# Adafruit_Proto_Doubler_PiCowbell.net
KiCad netlist of a schematic drawn in EAGLE
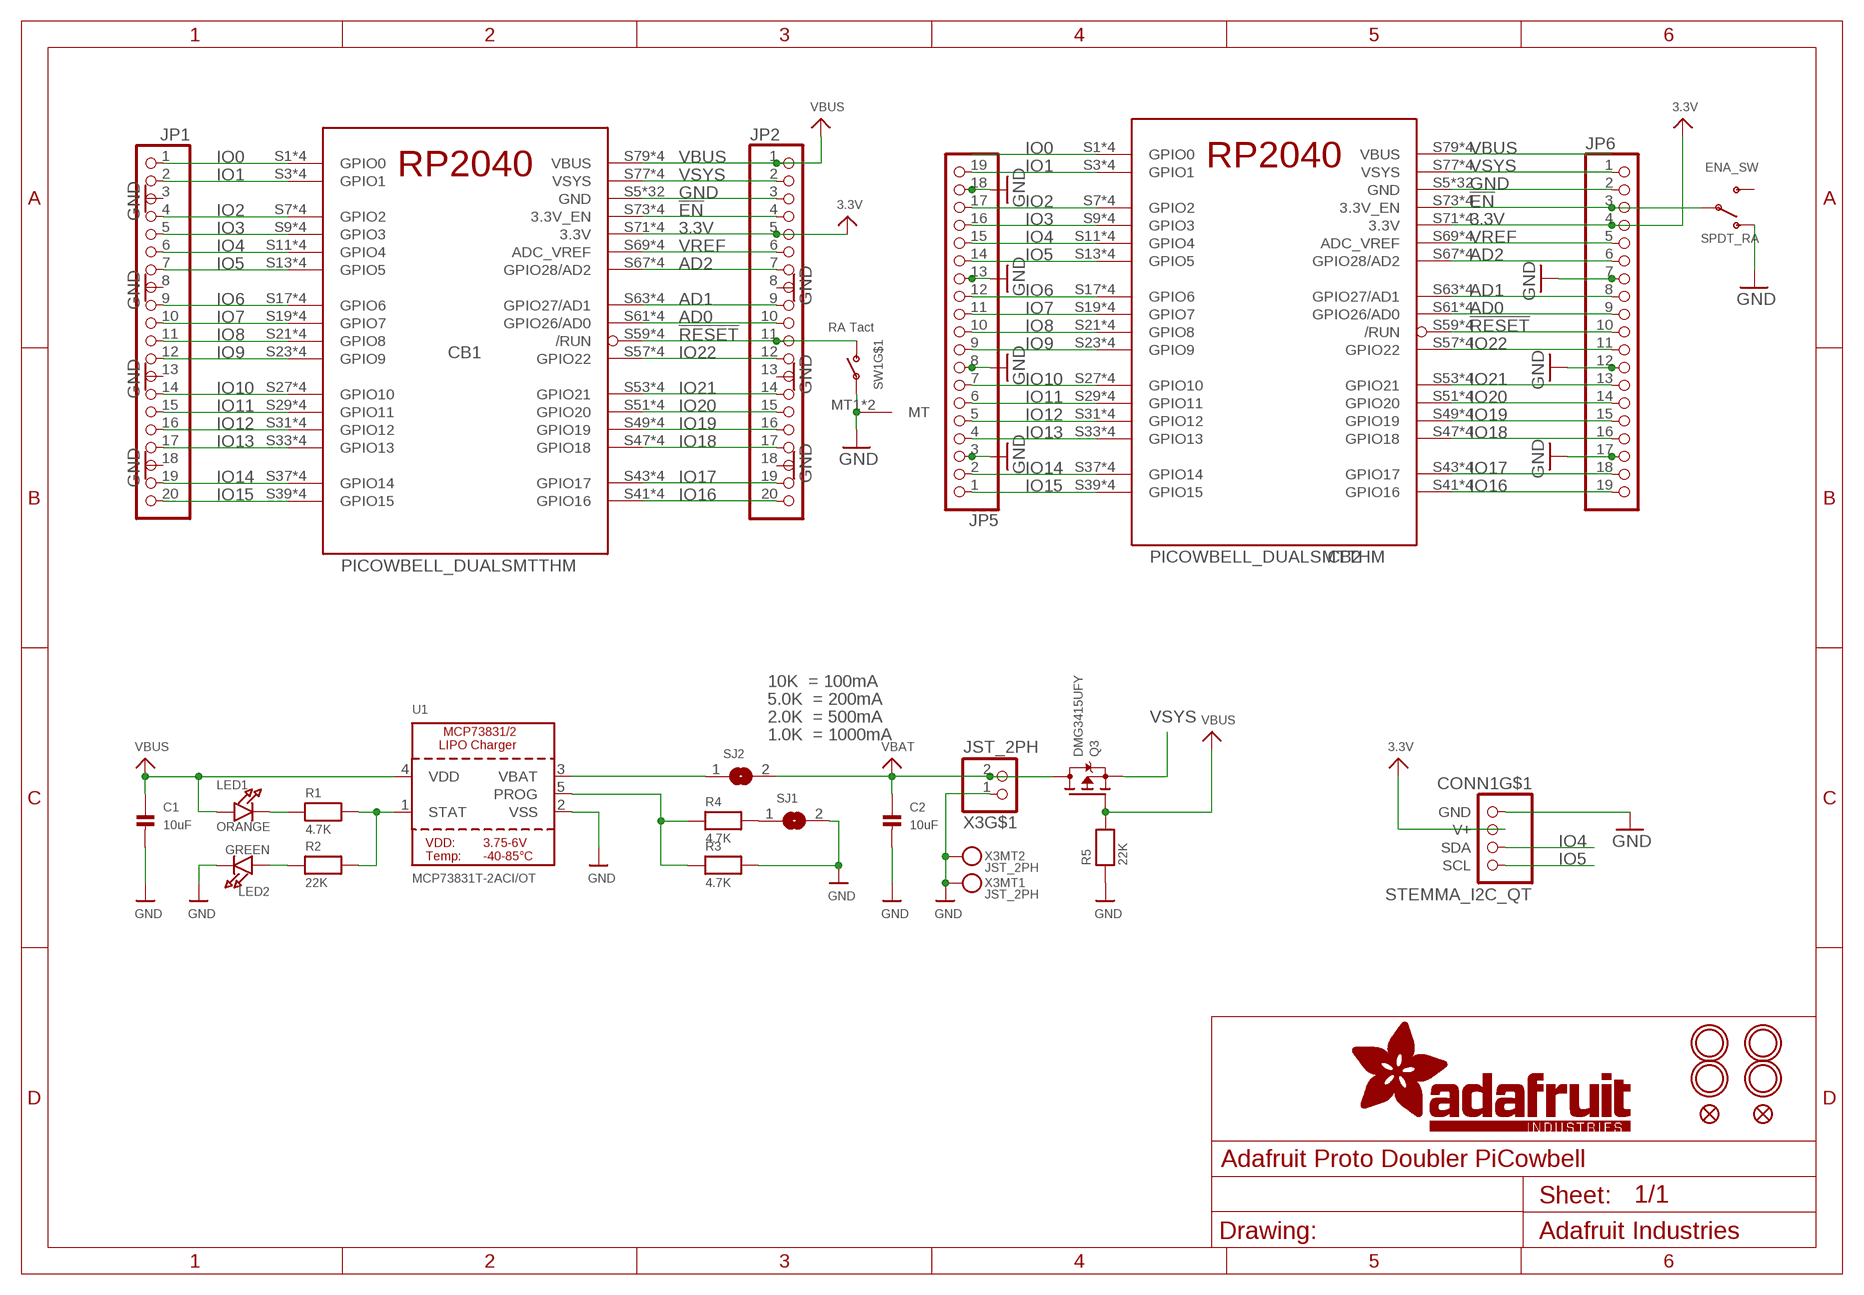
[diagram p0: schematic, sheet 1]

(export (version "E")
  (design (tool "Eeschema 10.0.6"))
  (components
    (comp (ref "C1")
      (value "10uF")
      (footprint "eagle-import:0805-NO")
      (libsource (lib "eagle-import") (part "CAP_CERAMIC0805-NOOUTLINE"))
    )
    (comp (ref "C2")
      (value "10uF")
      (footprint "eagle-import:0805-NO")
      (libsource (lib "eagle-import") (part "CAP_CERAMIC0805-NOOUTLINE"))
    )
    (comp (ref "CB1")
      (value "PICOWBELL_DUALSMTTHM")
      (footprint "eagle-import:PICOWBELL_DUALSMTTHM")
      (libsource (lib "eagle-import") (part "PICOWBELL_DUALSMTTHM"))
    )
    (comp (ref "CB2")
      (value "PICOWBELL_DUALSMTTHM")
      (footprint "eagle-import:PICOWBELL_DUALSMTTHM")
      (libsource (lib "eagle-import") (part "PICOWBELL_DUALSMTTHM"))
    )
    (comp (ref "CONN1")
      (value "STEMMA_I2C_QT")
      (footprint "eagle-import:JST_SH4")
      (libsource (lib "eagle-import") (part "STEMMA_I2C_QT"))
    )
    (comp (ref "ENA_SW")
      (value "SPDT_RA")
      (footprint "eagle-import:SPDT_SMT_SSSS811101")
      (libsource (lib "eagle-import") (part "SWITCH_SPDT"))
    )
    (comp (ref "FID1")
      (value "FIDUCIAL_1MM")
      (footprint "eagle-import:FIDUCIAL_1MM")
      (libsource (lib "eagle-import") (part "FIDUCIAL_1MM"))
    )
    (comp (ref "FID2")
      (value "FIDUCIAL_1MM")
      (footprint "eagle-import:FIDUCIAL_1MM")
      (libsource (lib "eagle-import") (part "FIDUCIAL_1MM"))
    )
    (comp (ref "JP1")
      (value "HEADER-1X20_70MIL")
      (footprint "eagle-import:1X20_ROUND_70MIL")
      (libsource (lib "eagle-import") (part "HEADER-1X20_70MIL"))
    )
    (comp (ref "JP2")
      (value "HEADER-1X20_70MIL")
      (footprint "eagle-import:1X20_ROUND_70MIL")
      (libsource (lib "eagle-import") (part "HEADER-1X20_70MIL"))
    )
    (comp (ref "JP5")
      (value "HEADER-1X19")
      (footprint "eagle-import:1X19_ROUND")
      (libsource (lib "eagle-import") (part "HEADER-1X19"))
    )
    (comp (ref "JP6")
      (value "HEADER-1X19")
      (footprint "eagle-import:1X19_ROUND")
      (libsource (lib "eagle-import") (part "HEADER-1X19"))
    )
    (comp (ref "LED1")
      (value "ORANGE")
      (footprint "eagle-import:CHIPLED_0603_NOOUTLINE")
      (libsource (lib "eagle-import") (part "LED0603_NOOUTLINE"))
    )
    (comp (ref "LED2")
      (value "GREEN")
      (footprint "eagle-import:CHIPLED_0603_NOOUTLINE")
      (libsource (lib "eagle-import") (part "LED0603_NOOUTLINE"))
    )
    (comp (ref "Q3")
      (value "DMG3415UFY")
      (footprint "eagle-import:DFN2015-3")
      (libsource (lib "eagle-import") (part "MOSFET-P_DFN2015"))
    )
    (comp (ref "R1")
      (value "4.7K")
      (footprint "eagle-import:_0402NO")
      (libsource (lib "eagle-import") (part "RESISTOR_0402NO"))
    )
    (comp (ref "R2")
      (value "22K")
      (footprint "eagle-import:_0402NO")
      (libsource (lib "eagle-import") (part "RESISTOR_0402NO"))
    )
    (comp (ref "R3")
      (value "4.7K")
      (footprint "eagle-import:_0402NO")
      (libsource (lib "eagle-import") (part "RESISTOR_0402NO"))
    )
    (comp (ref "R4")
      (value "4.7K")
      (footprint "eagle-import:_0402NO")
      (libsource (lib "eagle-import") (part "RESISTOR_0402NO"))
    )
    (comp (ref "R5")
      (value "22K")
      (footprint "eagle-import:_0402NO")
      (libsource (lib "eagle-import") (part "RESISTOR_0402NO"))
    )
    (comp (ref "SJ1")
      (value "SOLDERJUMPERCLOSED")
      (footprint "eagle-import:SOLDERJUMPER_CLOSEDWIRE")
      (libsource (lib "eagle-import") (part "SOLDERJUMPERCLOSED"))
    )
    (comp (ref "SJ2")
      (value "SOLDERJUMPERCLOSED")
      (footprint "eagle-import:SOLDERJUMPER_CLOSEDWIRE")
      (libsource (lib "eagle-import") (part "SOLDERJUMPERCLOSED"))
    )
    (comp (ref "SW1")
      (value "RA Tact")
      (footprint "eagle-import:SPST_TACTILE_RA")
      (libsource (lib "eagle-import") (part "SWITCH_SPST_MNT_TACT_RA"))
    )
    (comp (ref "U$5")
      (value "MOUNTINGHOLE2.5")
      (footprint "eagle-import:MOUNTINGHOLE_2.5_PLATED")
      (libsource (lib "eagle-import") (part "MOUNTINGHOLE2.5"))
    )
    (comp (ref "U$7")
      (value "MOUNTINGHOLE2.5")
      (footprint "eagle-import:MOUNTINGHOLE_2.5_PLATED")
      (libsource (lib "eagle-import") (part "MOUNTINGHOLE2.5"))
    )
    (comp (ref "U$15")
      (value "MOUNTINGHOLE2.5")
      (footprint "eagle-import:MOUNTINGHOLE_2.5_PLATED")
      (libsource (lib "eagle-import") (part "MOUNTINGHOLE2.5"))
    )
    (comp (ref "U$16")
      (value "MOUNTINGHOLE2.5")
      (footprint "eagle-import:MOUNTINGHOLE_2.5_PLATED")
      (libsource (lib "eagle-import") (part "MOUNTINGHOLE2.5"))
    )
    (comp (ref "U1")
      (value "MCP73831T-2ACI/OT")
      (footprint "eagle-import:SOT23-5")
      (fields (field (name "JLC_ROTATION") "0"))
      (libsource (lib "eagle-import") (part "MCP73831/2"))
    )
    (comp (ref "X3")
      (value "JST_2PH")
      (footprint "eagle-import:JSTPH2_BATT")
      (libsource (lib "eagle-import") (part "CON_JST_PH_2PIN_MT_BATT"))
    )
  )
  (nets
    (net (code "1") (name "/AD0") (class "Default")
      (node (ref "CB1") (pin "S61") (pinfunction "GPIO26/AD0_S61") (pintype "bidirectional"))
      (node (ref "CB1") (pin "S62") (pinfunction "GPIO26/AD0_S62") (pintype "bidirectional"))
      (node (ref "CB1") (pin "T61") (pinfunction "GPIO26/AD0_T61") (pintype "bidirectional"))
      (node (ref "CB1") (pin "T62") (pinfunction "GPIO26/AD0_T62") (pintype "bidirectional"))
      (node (ref "CB2") (pin "S61") (pinfunction "GPIO26/AD0_S61") (pintype "bidirectional"))
      (node (ref "CB2") (pin "S62") (pinfunction "GPIO26/AD0_S62") (pintype "bidirectional"))
      (node (ref "CB2") (pin "T61") (pinfunction "GPIO26/AD0_T61") (pintype "bidirectional"))
      (node (ref "CB2") (pin "T62") (pinfunction "GPIO26/AD0_T62") (pintype "bidirectional"))
      (node (ref "JP2") (pin "10") (pinfunction "10_10") (pintype "passive"))
      (node (ref "JP6") (pin "9") (pinfunction "9_9") (pintype "passive"))
    )
    (net (code "2") (name "/AD1") (class "Default")
      (node (ref "CB1") (pin "S63") (pinfunction "GPIO27/AD1_S63") (pintype "bidirectional"))
      (node (ref "CB1") (pin "S64") (pinfunction "GPIO27/AD1_S64") (pintype "bidirectional"))
      (node (ref "CB1") (pin "T63") (pinfunction "GPIO27/AD1_T63") (pintype "bidirectional"))
      (node (ref "CB1") (pin "T64") (pinfunction "GPIO27/AD1_T64") (pintype "bidirectional"))
      (node (ref "CB2") (pin "S63") (pinfunction "GPIO27/AD1_S63") (pintype "bidirectional"))
      (node (ref "CB2") (pin "S64") (pinfunction "GPIO27/AD1_S64") (pintype "bidirectional"))
      (node (ref "CB2") (pin "T63") (pinfunction "GPIO27/AD1_T63") (pintype "bidirectional"))
      (node (ref "CB2") (pin "T64") (pinfunction "GPIO27/AD1_T64") (pintype "bidirectional"))
      (node (ref "JP2") (pin "9") (pinfunction "9_9") (pintype "passive"))
      (node (ref "JP6") (pin "8") (pinfunction "8_8") (pintype "passive"))
    )
    (net (code "3") (name "/AD2") (class "Default")
      (node (ref "CB1") (pin "S67") (pinfunction "GPIO28/AD2_S67") (pintype "bidirectional"))
      (node (ref "CB1") (pin "S68") (pinfunction "GPIO28/AD2_S68") (pintype "bidirectional"))
      (node (ref "CB1") (pin "T67") (pinfunction "GPIO28/AD2_T67") (pintype "bidirectional"))
      (node (ref "CB1") (pin "T68") (pinfunction "GPIO28/AD2_T68") (pintype "bidirectional"))
      (node (ref "CB2") (pin "S67") (pinfunction "GPIO28/AD2_S67") (pintype "bidirectional"))
      (node (ref "CB2") (pin "S68") (pinfunction "GPIO28/AD2_S68") (pintype "bidirectional"))
      (node (ref "CB2") (pin "T67") (pinfunction "GPIO28/AD2_T67") (pintype "bidirectional"))
      (node (ref "CB2") (pin "T68") (pinfunction "GPIO28/AD2_T68") (pintype "bidirectional"))
      (node (ref "JP2") (pin "7") (pinfunction "7_7") (pintype "passive"))
      (node (ref "JP6") (pin "6") (pinfunction "6_6") (pintype "passive"))
    )
    (net (code "4") (name "/IO0") (class "Default")
      (node (ref "CB1") (pin "S1") (pinfunction "GPIO0_S1") (pintype "bidirectional"))
      (node (ref "CB1") (pin "S2") (pinfunction "GPIO0_S2") (pintype "bidirectional"))
      (node (ref "CB1") (pin "T1") (pinfunction "GPIO0_T1") (pintype "bidirectional"))
      (node (ref "CB1") (pin "T2") (pinfunction "GPIO0_T2") (pintype "bidirectional"))
      (node (ref "CB2") (pin "S1") (pinfunction "GPIO0_S1") (pintype "bidirectional"))
      (node (ref "CB2") (pin "S2") (pinfunction "GPIO0_S2") (pintype "bidirectional"))
      (node (ref "CB2") (pin "T1") (pinfunction "GPIO0_T1") (pintype "bidirectional"))
      (node (ref "CB2") (pin "T2") (pinfunction "GPIO0_T2") (pintype "bidirectional"))
      (node (ref "JP1") (pin "1") (pinfunction "1_1") (pintype "passive"))
    )
    (net (code "5") (name "/IO1") (class "Default")
      (node (ref "CB1") (pin "S3") (pinfunction "GPIO1_S3") (pintype "bidirectional"))
      (node (ref "CB1") (pin "S4") (pinfunction "GPIO1_S4") (pintype "bidirectional"))
      (node (ref "CB1") (pin "T3") (pinfunction "GPIO1_T3") (pintype "bidirectional"))
      (node (ref "CB1") (pin "T4") (pinfunction "GPIO1_T4") (pintype "bidirectional"))
      (node (ref "CB2") (pin "S3") (pinfunction "GPIO1_S3") (pintype "bidirectional"))
      (node (ref "CB2") (pin "S4") (pinfunction "GPIO1_S4") (pintype "bidirectional"))
      (node (ref "CB2") (pin "T3") (pinfunction "GPIO1_T3") (pintype "bidirectional"))
      (node (ref "CB2") (pin "T4") (pinfunction "GPIO1_T4") (pintype "bidirectional"))
      (node (ref "JP1") (pin "2") (pinfunction "2_2") (pintype "passive"))
      (node (ref "JP5") (pin "19") (pinfunction "19_19") (pintype "passive"))
    )
    (net (code "6") (name "/IO2") (class "Default")
      (node (ref "CB1") (pin "S7") (pinfunction "GPIO2_S7") (pintype "bidirectional"))
      (node (ref "CB1") (pin "S8") (pinfunction "GPIO2_S8") (pintype "bidirectional"))
      (node (ref "CB1") (pin "T7") (pinfunction "GPIO2_T7") (pintype "bidirectional"))
      (node (ref "CB1") (pin "T8") (pinfunction "GPIO2_T8") (pintype "bidirectional"))
      (node (ref "CB2") (pin "S7") (pinfunction "GPIO2_S7") (pintype "bidirectional"))
      (node (ref "CB2") (pin "S8") (pinfunction "GPIO2_S8") (pintype "bidirectional"))
      (node (ref "CB2") (pin "T7") (pinfunction "GPIO2_T7") (pintype "bidirectional"))
      (node (ref "CB2") (pin "T8") (pinfunction "GPIO2_T8") (pintype "bidirectional"))
      (node (ref "JP1") (pin "4") (pinfunction "4_4") (pintype "passive"))
      (node (ref "JP5") (pin "17") (pinfunction "17_17") (pintype "passive"))
    )
    (net (code "7") (name "/IO3") (class "Default")
      (node (ref "CB1") (pin "S10") (pinfunction "GPIO3_S10") (pintype "bidirectional"))
      (node (ref "CB1") (pin "S9") (pinfunction "GPIO3_S9") (pintype "bidirectional"))
      (node (ref "CB1") (pin "T10") (pinfunction "GPIO3_T10") (pintype "bidirectional"))
      (node (ref "CB1") (pin "T9") (pinfunction "GPIO3_T9") (pintype "bidirectional"))
      (node (ref "CB2") (pin "S10") (pinfunction "GPIO3_S10") (pintype "bidirectional"))
      (node (ref "CB2") (pin "S9") (pinfunction "GPIO3_S9") (pintype "bidirectional"))
      (node (ref "CB2") (pin "T10") (pinfunction "GPIO3_T10") (pintype "bidirectional"))
      (node (ref "CB2") (pin "T9") (pinfunction "GPIO3_T9") (pintype "bidirectional"))
      (node (ref "JP1") (pin "5") (pinfunction "5_5") (pintype "passive"))
      (node (ref "JP5") (pin "16") (pinfunction "16_16") (pintype "passive"))
    )
    (net (code "8") (name "/IO4") (class "Default")
      (node (ref "CB1") (pin "S11") (pinfunction "GPIO4_S11") (pintype "bidirectional"))
      (node (ref "CB1") (pin "S12") (pinfunction "GPIO4_S12") (pintype "bidirectional"))
      (node (ref "CB1") (pin "T11") (pinfunction "GPIO4_T11") (pintype "bidirectional"))
      (node (ref "CB1") (pin "T12") (pinfunction "GPIO4_T12") (pintype "bidirectional"))
      (node (ref "CB2") (pin "S11") (pinfunction "GPIO4_S11") (pintype "bidirectional"))
      (node (ref "CB2") (pin "S12") (pinfunction "GPIO4_S12") (pintype "bidirectional"))
      (node (ref "CB2") (pin "T11") (pinfunction "GPIO4_T11") (pintype "bidirectional"))
      (node (ref "CB2") (pin "T12") (pinfunction "GPIO4_T12") (pintype "bidirectional"))
      (node (ref "CONN1") (pin "3") (pinfunction "SDA_3") (pintype "passive"))
      (node (ref "JP1") (pin "6") (pinfunction "6_6") (pintype "passive"))
      (node (ref "JP5") (pin "15") (pinfunction "15_15") (pintype "passive"))
    )
    (net (code "9") (name "/IO5") (class "Default")
      (node (ref "CB1") (pin "S13") (pinfunction "GPIO5_S13") (pintype "bidirectional"))
      (node (ref "CB1") (pin "S14") (pinfunction "GPIO5_S14") (pintype "bidirectional"))
      (node (ref "CB1") (pin "T13") (pinfunction "GPIO5_T13") (pintype "bidirectional"))
      (node (ref "CB1") (pin "T14") (pinfunction "GPIO5_T14") (pintype "bidirectional"))
      (node (ref "CB2") (pin "S13") (pinfunction "GPIO5_S13") (pintype "bidirectional"))
      (node (ref "CB2") (pin "S14") (pinfunction "GPIO5_S14") (pintype "bidirectional"))
      (node (ref "CB2") (pin "T13") (pinfunction "GPIO5_T13") (pintype "bidirectional"))
      (node (ref "CB2") (pin "T14") (pinfunction "GPIO5_T14") (pintype "bidirectional"))
      (node (ref "CONN1") (pin "4") (pinfunction "SCL_4") (pintype "passive"))
      (node (ref "JP1") (pin "7") (pinfunction "7_7") (pintype "passive"))
      (node (ref "JP5") (pin "14") (pinfunction "14_14") (pintype "passive"))
    )
    (net (code "10") (name "/IO6") (class "Default")
      (node (ref "CB1") (pin "S17") (pinfunction "GPIO6_S17") (pintype "bidirectional"))
      (node (ref "CB1") (pin "S18") (pinfunction "GPIO6_S18") (pintype "bidirectional"))
      (node (ref "CB1") (pin "T17") (pinfunction "GPIO6_T17") (pintype "bidirectional"))
      (node (ref "CB1") (pin "T18") (pinfunction "GPIO6_T18") (pintype "bidirectional"))
      (node (ref "CB2") (pin "S17") (pinfunction "GPIO6_S17") (pintype "bidirectional"))
      (node (ref "CB2") (pin "S18") (pinfunction "GPIO6_S18") (pintype "bidirectional"))
      (node (ref "CB2") (pin "T17") (pinfunction "GPIO6_T17") (pintype "bidirectional"))
      (node (ref "CB2") (pin "T18") (pinfunction "GPIO6_T18") (pintype "bidirectional"))
      (node (ref "JP1") (pin "9") (pinfunction "9_9") (pintype "passive"))
      (node (ref "JP5") (pin "12") (pinfunction "12_12") (pintype "passive"))
    )
    (net (code "11") (name "/IO7") (class "Default")
      (node (ref "CB1") (pin "S19") (pinfunction "GPIO7_S19") (pintype "bidirectional"))
      (node (ref "CB1") (pin "S20") (pinfunction "GPIO7_S20") (pintype "bidirectional"))
      (node (ref "CB1") (pin "T19") (pinfunction "GPIO7_T19") (pintype "bidirectional"))
      (node (ref "CB1") (pin "T20") (pinfunction "GPIO7_T20") (pintype "bidirectional"))
      (node (ref "CB2") (pin "S19") (pinfunction "GPIO7_S19") (pintype "bidirectional"))
      (node (ref "CB2") (pin "S20") (pinfunction "GPIO7_S20") (pintype "bidirectional"))
      (node (ref "CB2") (pin "T19") (pinfunction "GPIO7_T19") (pintype "bidirectional"))
      (node (ref "CB2") (pin "T20") (pinfunction "GPIO7_T20") (pintype "bidirectional"))
      (node (ref "JP1") (pin "10") (pinfunction "10_10") (pintype "passive"))
      (node (ref "JP5") (pin "11") (pinfunction "11_11") (pintype "passive"))
    )
    (net (code "12") (name "/IO8") (class "Default")
      (node (ref "CB1") (pin "S21") (pinfunction "GPIO8_S21") (pintype "bidirectional"))
      (node (ref "CB1") (pin "S22") (pinfunction "GPIO8_S22") (pintype "bidirectional"))
      (node (ref "CB1") (pin "T21") (pinfunction "GPIO8_T21") (pintype "bidirectional"))
      (node (ref "CB1") (pin "T22") (pinfunction "GPIO8_T22") (pintype "bidirectional"))
      (node (ref "CB2") (pin "S21") (pinfunction "GPIO8_S21") (pintype "bidirectional"))
      (node (ref "CB2") (pin "S22") (pinfunction "GPIO8_S22") (pintype "bidirectional"))
      (node (ref "CB2") (pin "T21") (pinfunction "GPIO8_T21") (pintype "bidirectional"))
      (node (ref "CB2") (pin "T22") (pinfunction "GPIO8_T22") (pintype "bidirectional"))
      (node (ref "JP1") (pin "11") (pinfunction "11_11") (pintype "passive"))
      (node (ref "JP5") (pin "10") (pinfunction "10_10") (pintype "passive"))
    )
    (net (code "13") (name "/IO9") (class "Default")
      (node (ref "CB1") (pin "S23") (pinfunction "GPIO9_S23") (pintype "bidirectional"))
      (node (ref "CB1") (pin "S24") (pinfunction "GPIO9_S24") (pintype "bidirectional"))
      (node (ref "CB1") (pin "T23") (pinfunction "GPIO9_T23") (pintype "bidirectional"))
      (node (ref "CB1") (pin "T24") (pinfunction "GPIO9_T24") (pintype "bidirectional"))
      (node (ref "CB2") (pin "S23") (pinfunction "GPIO9_S23") (pintype "bidirectional"))
      (node (ref "CB2") (pin "S24") (pinfunction "GPIO9_S24") (pintype "bidirectional"))
      (node (ref "CB2") (pin "T23") (pinfunction "GPIO9_T23") (pintype "bidirectional"))
      (node (ref "CB2") (pin "T24") (pinfunction "GPIO9_T24") (pintype "bidirectional"))
      (node (ref "JP1") (pin "12") (pinfunction "12_12") (pintype "passive"))
      (node (ref "JP5") (pin "9") (pinfunction "9_9") (pintype "passive"))
    )
    (net (code "14") (name "/IO10") (class "Default")
      (node (ref "CB1") (pin "S27") (pinfunction "GPIO10_S27") (pintype "bidirectional"))
      (node (ref "CB1") (pin "S28") (pinfunction "GPIO10_S28") (pintype "bidirectional"))
      (node (ref "CB1") (pin "T27") (pinfunction "GPIO10_T27") (pintype "bidirectional"))
      (node (ref "CB1") (pin "T28") (pinfunction "GPIO10_T28") (pintype "bidirectional"))
      (node (ref "CB2") (pin "S27") (pinfunction "GPIO10_S27") (pintype "bidirectional"))
      (node (ref "CB2") (pin "S28") (pinfunction "GPIO10_S28") (pintype "bidirectional"))
      (node (ref "CB2") (pin "T27") (pinfunction "GPIO10_T27") (pintype "bidirectional"))
      (node (ref "CB2") (pin "T28") (pinfunction "GPIO10_T28") (pintype "bidirectional"))
      (node (ref "JP1") (pin "14") (pinfunction "14_14") (pintype "passive"))
      (node (ref "JP5") (pin "7") (pinfunction "7_7") (pintype "passive"))
    )
    (net (code "15") (name "/IO11") (class "Default")
      (node (ref "CB1") (pin "S29") (pinfunction "GPIO11_S29") (pintype "bidirectional"))
      (node (ref "CB1") (pin "S30") (pinfunction "GPIO11_S30") (pintype "bidirectional"))
      (node (ref "CB1") (pin "T29") (pinfunction "GPIO11_T29") (pintype "bidirectional"))
      (node (ref "CB1") (pin "T30") (pinfunction "GPIO11_T30") (pintype "bidirectional"))
      (node (ref "CB2") (pin "S29") (pinfunction "GPIO11_S29") (pintype "bidirectional"))
      (node (ref "CB2") (pin "S30") (pinfunction "GPIO11_S30") (pintype "bidirectional"))
      (node (ref "CB2") (pin "T29") (pinfunction "GPIO11_T29") (pintype "bidirectional"))
      (node (ref "CB2") (pin "T30") (pinfunction "GPIO11_T30") (pintype "bidirectional"))
      (node (ref "JP1") (pin "15") (pinfunction "15_15") (pintype "passive"))
      (node (ref "JP5") (pin "6") (pinfunction "6_6") (pintype "passive"))
    )
    (net (code "16") (name "/IO12") (class "Default")
      (node (ref "CB1") (pin "S31") (pinfunction "GPIO12_S31") (pintype "bidirectional"))
      (node (ref "CB1") (pin "S32") (pinfunction "GPIO12_S32") (pintype "bidirectional"))
      (node (ref "CB1") (pin "T31") (pinfunction "GPIO12_T31") (pintype "bidirectional"))
      (node (ref "CB1") (pin "T32") (pinfunction "GPIO12_T32") (pintype "bidirectional"))
      (node (ref "CB2") (pin "S31") (pinfunction "GPIO12_S31") (pintype "bidirectional"))
      (node (ref "CB2") (pin "S32") (pinfunction "GPIO12_S32") (pintype "bidirectional"))
      (node (ref "CB2") (pin "T31") (pinfunction "GPIO12_T31") (pintype "bidirectional"))
      (node (ref "CB2") (pin "T32") (pinfunction "GPIO12_T32") (pintype "bidirectional"))
      (node (ref "JP1") (pin "16") (pinfunction "16_16") (pintype "passive"))
      (node (ref "JP5") (pin "5") (pinfunction "5_5") (pintype "passive"))
    )
    (net (code "17") (name "/IO13") (class "Default")
      (node (ref "CB1") (pin "S33") (pinfunction "GPIO13_S33") (pintype "bidirectional"))
      (node (ref "CB1") (pin "S34") (pinfunction "GPIO13_S34") (pintype "bidirectional"))
      (node (ref "CB1") (pin "T33") (pinfunction "GPIO13_T33") (pintype "bidirectional"))
      (node (ref "CB1") (pin "T34") (pinfunction "GPIO13_T34") (pintype "bidirectional"))
      (node (ref "CB2") (pin "S33") (pinfunction "GPIO13_S33") (pintype "bidirectional"))
      (node (ref "CB2") (pin "S34") (pinfunction "GPIO13_S34") (pintype "bidirectional"))
      (node (ref "CB2") (pin "T33") (pinfunction "GPIO13_T33") (pintype "bidirectional"))
      (node (ref "CB2") (pin "T34") (pinfunction "GPIO13_T34") (pintype "bidirectional"))
      (node (ref "JP1") (pin "17") (pinfunction "17_17") (pintype "passive"))
      (node (ref "JP5") (pin "4") (pinfunction "4_4") (pintype "passive"))
    )
    (net (code "18") (name "/IO14") (class "Default")
      (node (ref "CB1") (pin "S37") (pinfunction "GPIO14_S37") (pintype "bidirectional"))
      (node (ref "CB1") (pin "S38") (pinfunction "GPIO14_S38") (pintype "bidirectional"))
      (node (ref "CB1") (pin "T37") (pinfunction "GPIO14_T37") (pintype "bidirectional"))
      (node (ref "CB1") (pin "T38") (pinfunction "GPIO14_T38") (pintype "bidirectional"))
      (node (ref "CB2") (pin "S37") (pinfunction "GPIO14_S37") (pintype "bidirectional"))
      (node (ref "CB2") (pin "S38") (pinfunction "GPIO14_S38") (pintype "bidirectional"))
      (node (ref "CB2") (pin "T37") (pinfunction "GPIO14_T37") (pintype "bidirectional"))
      (node (ref "CB2") (pin "T38") (pinfunction "GPIO14_T38") (pintype "bidirectional"))
      (node (ref "JP1") (pin "19") (pinfunction "19_19") (pintype "passive"))
      (node (ref "JP5") (pin "2") (pinfunction "2_2") (pintype "passive"))
    )
    (net (code "19") (name "/IO15") (class "Default")
      (node (ref "CB1") (pin "S39") (pinfunction "GPIO15_S39") (pintype "bidirectional"))
      (node (ref "CB1") (pin "S40") (pinfunction "GPIO15_S40") (pintype "bidirectional"))
      (node (ref "CB1") (pin "T39") (pinfunction "GPIO15_T39") (pintype "bidirectional"))
      (node (ref "CB1") (pin "T40") (pinfunction "GPIO15_T40") (pintype "bidirectional"))
      (node (ref "CB2") (pin "S39") (pinfunction "GPIO15_S39") (pintype "bidirectional"))
      (node (ref "CB2") (pin "S40") (pinfunction "GPIO15_S40") (pintype "bidirectional"))
      (node (ref "CB2") (pin "T39") (pinfunction "GPIO15_T39") (pintype "bidirectional"))
      (node (ref "CB2") (pin "T40") (pinfunction "GPIO15_T40") (pintype "bidirectional"))
      (node (ref "JP1") (pin "20") (pinfunction "20_20") (pintype "passive"))
      (node (ref "JP5") (pin "1") (pinfunction "1_1") (pintype "passive"))
    )
    (net (code "20") (name "/IO16") (class "Default")
      (node (ref "CB1") (pin "S41") (pinfunction "GPIO16_S41") (pintype "bidirectional"))
      (node (ref "CB1") (pin "S42") (pinfunction "GPIO16_S42") (pintype "bidirectional"))
      (node (ref "CB1") (pin "T41") (pinfunction "GPIO16_T41") (pintype "bidirectional"))
      (node (ref "CB1") (pin "T42") (pinfunction "GPIO16_T42") (pintype "bidirectional"))
      (node (ref "CB2") (pin "S41") (pinfunction "GPIO16_S41") (pintype "bidirectional"))
      (node (ref "CB2") (pin "S42") (pinfunction "GPIO16_S42") (pintype "bidirectional"))
      (node (ref "CB2") (pin "T41") (pinfunction "GPIO16_T41") (pintype "bidirectional"))
      (node (ref "CB2") (pin "T42") (pinfunction "GPIO16_T42") (pintype "bidirectional"))
      (node (ref "JP2") (pin "20") (pinfunction "20_20") (pintype "passive"))
      (node (ref "JP6") (pin "19") (pinfunction "19_19") (pintype "passive"))
    )
    (net (code "21") (name "/IO17") (class "Default")
      (node (ref "CB1") (pin "S43") (pinfunction "GPIO17_S43") (pintype "bidirectional"))
      (node (ref "CB1") (pin "S44") (pinfunction "GPIO17_S44") (pintype "bidirectional"))
      (node (ref "CB1") (pin "T43") (pinfunction "GPIO17_T43") (pintype "bidirectional"))
      (node (ref "CB1") (pin "T44") (pinfunction "GPIO17_T44") (pintype "bidirectional"))
      (node (ref "CB2") (pin "S43") (pinfunction "GPIO17_S43") (pintype "bidirectional"))
      (node (ref "CB2") (pin "S44") (pinfunction "GPIO17_S44") (pintype "bidirectional"))
      (node (ref "CB2") (pin "T43") (pinfunction "GPIO17_T43") (pintype "bidirectional"))
      (node (ref "CB2") (pin "T44") (pinfunction "GPIO17_T44") (pintype "bidirectional"))
      (node (ref "JP2") (pin "19") (pinfunction "19_19") (pintype "passive"))
      (node (ref "JP6") (pin "18") (pinfunction "18_18") (pintype "passive"))
    )
    (net (code "22") (name "/IO18") (class "Default")
      (node (ref "CB1") (pin "S47") (pinfunction "GPIO18_S47") (pintype "bidirectional"))
      (node (ref "CB1") (pin "S48") (pinfunction "GPIO18_S48") (pintype "bidirectional"))
      (node (ref "CB1") (pin "T47") (pinfunction "GPIO18_T47") (pintype "bidirectional"))
      (node (ref "CB1") (pin "T48") (pinfunction "GPIO18_T48") (pintype "bidirectional"))
      (node (ref "CB2") (pin "S47") (pinfunction "GPIO18_S47") (pintype "bidirectional"))
      (node (ref "CB2") (pin "S48") (pinfunction "GPIO18_S48") (pintype "bidirectional"))
      (node (ref "CB2") (pin "T47") (pinfunction "GPIO18_T47") (pintype "bidirectional"))
      (node (ref "CB2") (pin "T48") (pinfunction "GPIO18_T48") (pintype "bidirectional"))
      (node (ref "JP2") (pin "17") (pinfunction "17_17") (pintype "passive"))
      (node (ref "JP6") (pin "16") (pinfunction "16_16") (pintype "passive"))
    )
    (net (code "23") (name "/IO19") (class "Default")
      (node (ref "CB1") (pin "S49") (pinfunction "GPIO19_S49") (pintype "bidirectional"))
      (node (ref "CB1") (pin "S50") (pinfunction "GPIO19_S50") (pintype "bidirectional"))
      (node (ref "CB1") (pin "T49") (pinfunction "GPIO19_T49") (pintype "bidirectional"))
      (node (ref "CB1") (pin "T50") (pinfunction "GPIO19_T50") (pintype "bidirectional"))
      (node (ref "CB2") (pin "S49") (pinfunction "GPIO19_S49") (pintype "bidirectional"))
      (node (ref "CB2") (pin "S50") (pinfunction "GPIO19_S50") (pintype "bidirectional"))
      (node (ref "CB2") (pin "T49") (pinfunction "GPIO19_T49") (pintype "bidirectional"))
      (node (ref "CB2") (pin "T50") (pinfunction "GPIO19_T50") (pintype "bidirectional"))
      (node (ref "JP2") (pin "16") (pinfunction "16_16") (pintype "passive"))
      (node (ref "JP6") (pin "15") (pinfunction "15_15") (pintype "passive"))
    )
    (net (code "24") (name "/IO20") (class "Default")
      (node (ref "CB1") (pin "S51") (pinfunction "GPIO20_S51") (pintype "bidirectional"))
      (node (ref "CB1") (pin "S52") (pinfunction "GPIO20_S52") (pintype "bidirectional"))
      (node (ref "CB1") (pin "T51") (pinfunction "GPIO20_T51") (pintype "bidirectional"))
      (node (ref "CB1") (pin "T52") (pinfunction "GPIO20_T52") (pintype "bidirectional"))
      (node (ref "CB2") (pin "S51") (pinfunction "GPIO20_S51") (pintype "bidirectional"))
      (node (ref "CB2") (pin "S52") (pinfunction "GPIO20_S52") (pintype "bidirectional"))
      (node (ref "CB2") (pin "T51") (pinfunction "GPIO20_T51") (pintype "bidirectional"))
      (node (ref "CB2") (pin "T52") (pinfunction "GPIO20_T52") (pintype "bidirectional"))
      (node (ref "JP2") (pin "15") (pinfunction "15_15") (pintype "passive"))
      (node (ref "JP6") (pin "14") (pinfunction "14_14") (pintype "passive"))
    )
    (net (code "25") (name "/IO21") (class "Default")
      (node (ref "CB1") (pin "S53") (pinfunction "GPIO21_S53") (pintype "bidirectional"))
      (node (ref "CB1") (pin "S54") (pinfunction "GPIO21_S54") (pintype "bidirectional"))
      (node (ref "CB1") (pin "T53") (pinfunction "GPIO21_T53") (pintype "bidirectional"))
      (node (ref "CB1") (pin "T54") (pinfunction "GPIO21_T54") (pintype "bidirectional"))
      (node (ref "CB2") (pin "S53") (pinfunction "GPIO21_S53") (pintype "bidirectional"))
      (node (ref "CB2") (pin "S54") (pinfunction "GPIO21_S54") (pintype "bidirectional"))
      (node (ref "CB2") (pin "T53") (pinfunction "GPIO21_T53") (pintype "bidirectional"))
      (node (ref "CB2") (pin "T54") (pinfunction "GPIO21_T54") (pintype "bidirectional"))
      (node (ref "JP2") (pin "14") (pinfunction "14_14") (pintype "passive"))
      (node (ref "JP6") (pin "13") (pinfunction "13_13") (pintype "passive"))
    )
    (net (code "26") (name "/IO22") (class "Default")
      (node (ref "CB1") (pin "S57") (pinfunction "GPIO22_S57") (pintype "bidirectional"))
      (node (ref "CB1") (pin "S58") (pinfunction "GPIO22_S58") (pintype "bidirectional"))
      (node (ref "CB1") (pin "T57") (pinfunction "GPIO22_T57") (pintype "bidirectional"))
      (node (ref "CB1") (pin "T58") (pinfunction "GPIO22_T58") (pintype "bidirectional"))
      (node (ref "CB2") (pin "S57") (pinfunction "GPIO22_S57") (pintype "bidirectional"))
      (node (ref "CB2") (pin "S58") (pinfunction "GPIO22_S58") (pintype "bidirectional"))
      (node (ref "CB2") (pin "T57") (pinfunction "GPIO22_T57") (pintype "bidirectional"))
      (node (ref "CB2") (pin "T58") (pinfunction "GPIO22_T58") (pintype "bidirectional"))
      (node (ref "JP2") (pin "12") (pinfunction "12_12") (pintype "passive"))
      (node (ref "JP6") (pin "11") (pinfunction "11_11") (pintype "passive"))
    )
    (net (code "27") (name "/VREF") (class "Default")
      (node (ref "CB1") (pin "S69") (pinfunction "ADC_VREF_S69") (pintype "passive"))
      (node (ref "CB1") (pin "S70") (pinfunction "ADC_VREF_S70") (pintype "passive"))
      (node (ref "CB1") (pin "T69") (pinfunction "ADC_VREF_T69") (pintype "passive"))
      (node (ref "CB1") (pin "T70") (pinfunction "ADC_VREF_T70") (pintype "passive"))
      (node (ref "CB2") (pin "S69") (pinfunction "ADC_VREF_S69") (pintype "passive"))
      (node (ref "CB2") (pin "S70") (pinfunction "ADC_VREF_S70") (pintype "passive"))
      (node (ref "CB2") (pin "T69") (pinfunction "ADC_VREF_T69") (pintype "passive"))
      (node (ref "CB2") (pin "T70") (pinfunction "ADC_VREF_T70") (pintype "passive"))
      (node (ref "JP2") (pin "6") (pinfunction "6_6") (pintype "passive"))
      (node (ref "JP6") (pin "5") (pinfunction "5_5") (pintype "passive"))
    )
    (net (code "28") (name "/VSYS") (class "Default")
      (node (ref "CB1") (pin "S77") (pinfunction "VSYS_S77") (pintype "power_in"))
      (node (ref "CB1") (pin "S78") (pinfunction "VSYS_S78") (pintype "power_in"))
      (node (ref "CB1") (pin "T77") (pinfunction "VSYS_T77") (pintype "power_in"))
      (node (ref "CB1") (pin "T78") (pinfunction "VSYS_T78") (pintype "power_in"))
      (node (ref "CB2") (pin "S77") (pinfunction "VSYS_S77") (pintype "power_in"))
      (node (ref "CB2") (pin "S78") (pinfunction "VSYS_S78") (pintype "power_in"))
      (node (ref "CB2") (pin "T77") (pinfunction "VSYS_T77") (pintype "power_in"))
      (node (ref "CB2") (pin "T78") (pinfunction "VSYS_T78") (pintype "power_in"))
      (node (ref "JP2") (pin "2") (pinfunction "2_2") (pintype "passive"))
      (node (ref "JP6") (pin "1") (pinfunction "1_1") (pintype "passive"))
      (node (ref "Q3") (pin "2") (pinfunction "S_2") (pintype "passive"))
    )
    (net (code "29") (name "/~{EN}") (class "Default")
      (node (ref "CB1") (pin "S73") (pinfunction "3.3V_EN_S73") (pintype "passive"))
      (node (ref "CB1") (pin "S74") (pinfunction "3.3V_EN_S74") (pintype "passive"))
      (node (ref "CB1") (pin "T73") (pinfunction "3.3V_EN_T73") (pintype "passive"))
      (node (ref "CB1") (pin "T74") (pinfunction "3.3V_EN_T74") (pintype "passive"))
      (node (ref "CB2") (pin "S73") (pinfunction "3.3V_EN_S73") (pintype "passive"))
      (node (ref "CB2") (pin "S74") (pinfunction "3.3V_EN_S74") (pintype "passive"))
      (node (ref "CB2") (pin "T73") (pinfunction "3.3V_EN_T73") (pintype "passive"))
      (node (ref "CB2") (pin "T74") (pinfunction "3.3V_EN_T74") (pintype "passive"))
      (node (ref "ENA_SW") (pin "B") (pinfunction "P_B") (pintype "passive"))
      (node (ref "JP2") (pin "4") (pinfunction "4_4") (pintype "passive"))
      (node (ref "JP6") (pin "3") (pinfunction "3_3") (pintype "passive"))
    )
    (net (code "30") (name "/~{RESET}") (class "Default")
      (node (ref "CB1") (pin "S59") (pinfunction "/RUN_S59") (pintype "bidirectional"))
      (node (ref "CB1") (pin "S60") (pinfunction "/RUN_S60") (pintype "bidirectional"))
      (node (ref "CB1") (pin "T59") (pinfunction "/RUN_T59") (pintype "bidirectional"))
      (node (ref "CB1") (pin "T60") (pinfunction "/RUN_T60") (pintype "bidirectional"))
      (node (ref "CB2") (pin "S59") (pinfunction "/RUN_S59") (pintype "bidirectional"))
      (node (ref "CB2") (pin "S60") (pinfunction "/RUN_S60") (pintype "bidirectional"))
      (node (ref "CB2") (pin "T59") (pinfunction "/RUN_T59") (pintype "bidirectional"))
      (node (ref "CB2") (pin "T60") (pinfunction "/RUN_T60") (pintype "bidirectional"))
      (node (ref "JP2") (pin "11") (pinfunction "11_11") (pintype "passive"))
      (node (ref "JP6") (pin "10") (pinfunction "10_10") (pintype "passive"))
      (node (ref "SW1") (pin "2") (pinfunction "S_2") (pintype "passive"))
    )
    (net (code "31") (name "3.3V") (class "Default")
      (node (ref "CB1") (pin "S71") (pinfunction "3.3V_S71") (pintype "power_in"))
      (node (ref "CB1") (pin "S72") (pinfunction "3.3V_S72") (pintype "power_in"))
      (node (ref "CB1") (pin "T71") (pinfunction "3.3V_T71") (pintype "power_in"))
      (node (ref "CB1") (pin "T72") (pinfunction "3.3V_T72") (pintype "power_in"))
      (node (ref "CB2") (pin "S71") (pinfunction "3.3V_S71") (pintype "power_in"))
      (node (ref "CB2") (pin "S72") (pinfunction "3.3V_S72") (pintype "power_in"))
      (node (ref "CB2") (pin "T71") (pinfunction "3.3V_T71") (pintype "power_in"))
      (node (ref "CB2") (pin "T72") (pinfunction "3.3V_T72") (pintype "power_in"))
      (node (ref "CONN1") (pin "2") (pinfunction "V+_2") (pintype "passive"))
      (node (ref "JP2") (pin "5") (pinfunction "5_5") (pintype "passive"))
      (node (ref "JP6") (pin "4") (pinfunction "4_4") (pintype "passive"))
    )
    (net (code "32") (name "GND") (class "Default")
      (node (ref "C1") (pin "2") (pinfunction "2_2") (pintype "passive"))
      (node (ref "C2") (pin "2") (pinfunction "2_2") (pintype "passive"))
      (node (ref "CB1") (pin "S15") (pinfunction "GND_S15") (pintype "power_in"))
      (node (ref "CB1") (pin "S16") (pinfunction "GND_S16") (pintype "power_in"))
      (node (ref "CB1") (pin "S25") (pinfunction "GND_S25") (pintype "power_in"))
      (node (ref "CB1") (pin "S26") (pinfunction "GND_S26") (pintype "power_in"))
      (node (ref "CB1") (pin "S35") (pinfunction "GND_S35") (pintype "power_in"))
      (node (ref "CB1") (pin "S36") (pinfunction "GND_S36") (pintype "power_in"))
      (node (ref "CB1") (pin "S45") (pinfunction "GND_S45") (pintype "power_in"))
      (node (ref "CB1") (pin "S46") (pinfunction "GND_S46") (pintype "power_in"))
      (node (ref "CB1") (pin "S5") (pinfunction "GND_S5") (pintype "power_in"))
      (node (ref "CB1") (pin "S55") (pinfunction "GND_S55") (pintype "power_in"))
      (node (ref "CB1") (pin "S56") (pinfunction "GND_S56") (pintype "power_in"))
      (node (ref "CB1") (pin "S6") (pinfunction "GND_S6") (pintype "power_in"))
      (node (ref "CB1") (pin "S65") (pinfunction "GND_S65") (pintype "power_in"))
      (node (ref "CB1") (pin "S66") (pinfunction "GND_S66") (pintype "power_in"))
      (node (ref "CB1") (pin "S75") (pinfunction "GND_S75") (pintype "power_in"))
      (node (ref "CB1") (pin "S76") (pinfunction "GND_S76") (pintype "power_in"))
      (node (ref "CB1") (pin "T15") (pinfunction "GND_T15") (pintype "power_in"))
      (node (ref "CB1") (pin "T16") (pinfunction "GND_T16") (pintype "power_in"))
      (node (ref "CB1") (pin "T25") (pinfunction "GND_T25") (pintype "power_in"))
      (node (ref "CB1") (pin "T26") (pinfunction "GND_T26") (pintype "power_in"))
      (node (ref "CB1") (pin "T35") (pinfunction "GND_T35") (pintype "power_in"))
      (node (ref "CB1") (pin "T36") (pinfunction "GND_T36") (pintype "power_in"))
      (node (ref "CB1") (pin "T45") (pinfunction "GND_T45") (pintype "power_in"))
      (node (ref "CB1") (pin "T46") (pinfunction "GND_T46") (pintype "power_in"))
      (node (ref "CB1") (pin "T5") (pinfunction "GND_T5") (pintype "power_in"))
      (node (ref "CB1") (pin "T55") (pinfunction "GND_T55") (pintype "power_in"))
      (node (ref "CB1") (pin "T56") (pinfunction "GND_T56") (pintype "power_in"))
      (node (ref "CB1") (pin "T6") (pinfunction "GND_T6") (pintype "power_in"))
      (node (ref "CB1") (pin "T65") (pinfunction "GND_T65") (pintype "power_in"))
      (node (ref "CB1") (pin "T66") (pinfunction "GND_T66") (pintype "power_in"))
      (node (ref "CB1") (pin "T75") (pinfunction "GND_T75") (pintype "power_in"))
      (node (ref "CB1") (pin "T76") (pinfunction "GND_T76") (pintype "power_in"))
      (node (ref "CB2") (pin "S15") (pinfunction "GND_S15") (pintype "power_in"))
      (node (ref "CB2") (pin "S16") (pinfunction "GND_S16") (pintype "power_in"))
      (node (ref "CB2") (pin "S25") (pinfunction "GND_S25") (pintype "power_in"))
      (node (ref "CB2") (pin "S26") (pinfunction "GND_S26") (pintype "power_in"))
      (node (ref "CB2") (pin "S35") (pinfunction "GND_S35") (pintype "power_in"))
      (node (ref "CB2") (pin "S36") (pinfunction "GND_S36") (pintype "power_in"))
      (node (ref "CB2") (pin "S45") (pinfunction "GND_S45") (pintype "power_in"))
      (node (ref "CB2") (pin "S46") (pinfunction "GND_S46") (pintype "power_in"))
      (node (ref "CB2") (pin "S5") (pinfunction "GND_S5") (pintype "power_in"))
      (node (ref "CB2") (pin "S55") (pinfunction "GND_S55") (pintype "power_in"))
      (node (ref "CB2") (pin "S56") (pinfunction "GND_S56") (pintype "power_in"))
      (node (ref "CB2") (pin "S6") (pinfunction "GND_S6") (pintype "power_in"))
      (node (ref "CB2") (pin "S65") (pinfunction "GND_S65") (pintype "power_in"))
      (node (ref "CB2") (pin "S66") (pinfunction "GND_S66") (pintype "power_in"))
      (node (ref "CB2") (pin "S75") (pinfunction "GND_S75") (pintype "power_in"))
      (node (ref "CB2") (pin "S76") (pinfunction "GND_S76") (pintype "power_in"))
      (node (ref "CB2") (pin "T15") (pinfunction "GND_T15") (pintype "power_in"))
      (node (ref "CB2") (pin "T16") (pinfunction "GND_T16") (pintype "power_in"))
      (node (ref "CB2") (pin "T25") (pinfunction "GND_T25") (pintype "power_in"))
      (node (ref "CB2") (pin "T26") (pinfunction "GND_T26") (pintype "power_in"))
      (node (ref "CB2") (pin "T35") (pinfunction "GND_T35") (pintype "power_in"))
      (node (ref "CB2") (pin "T36") (pinfunction "GND_T36") (pintype "power_in"))
      (node (ref "CB2") (pin "T45") (pinfunction "GND_T45") (pintype "power_in"))
      (node (ref "CB2") (pin "T46") (pinfunction "GND_T46") (pintype "power_in"))
      (node (ref "CB2") (pin "T5") (pinfunction "GND_T5") (pintype "power_in"))
      (node (ref "CB2") (pin "T55") (pinfunction "GND_T55") (pintype "power_in"))
      (node (ref "CB2") (pin "T56") (pinfunction "GND_T56") (pintype "power_in"))
      (node (ref "CB2") (pin "T6") (pinfunction "GND_T6") (pintype "power_in"))
      (node (ref "CB2") (pin "T65") (pinfunction "GND_T65") (pintype "power_in"))
      (node (ref "CB2") (pin "T66") (pinfunction "GND_T66") (pintype "power_in"))
      (node (ref "CB2") (pin "T75") (pinfunction "GND_T75") (pintype "power_in"))
      (node (ref "CB2") (pin "T76") (pinfunction "GND_T76") (pintype "power_in"))
      (node (ref "CONN1") (pin "1") (pinfunction "GND_1") (pintype "passive"))
      (node (ref "ENA_SW") (pin "A") (pinfunction "O_A") (pintype "passive"))
      (node (ref "JP1") (pin "13") (pinfunction "13_13") (pintype "passive"))
      (node (ref "JP1") (pin "18") (pinfunction "18_18") (pintype "passive"))
      (node (ref "JP1") (pin "3") (pinfunction "3_3") (pintype "passive"))
      (node (ref "JP1") (pin "8") (pinfunction "8_8") (pintype "passive"))
      (node (ref "JP2") (pin "13") (pinfunction "13_13") (pintype "passive"))
      (node (ref "JP2") (pin "18") (pinfunction "18_18") (pintype "passive"))
      (node (ref "JP2") (pin "3") (pinfunction "3_3") (pintype "passive"))
      (node (ref "JP2") (pin "8") (pinfunction "8_8") (pintype "passive"))
      (node (ref "JP5") (pin "13") (pinfunction "13_13") (pintype "passive"))
      (node (ref "JP5") (pin "18") (pinfunction "18_18") (pintype "passive"))
      (node (ref "JP5") (pin "3") (pinfunction "3_3") (pintype "passive"))
      (node (ref "JP5") (pin "8") (pinfunction "8_8") (pintype "passive"))
      (node (ref "JP6") (pin "12") (pinfunction "12_12") (pintype "passive"))
      (node (ref "JP6") (pin "17") (pinfunction "17_17") (pintype "passive"))
      (node (ref "JP6") (pin "2") (pinfunction "2_2") (pintype "passive"))
      (node (ref "JP6") (pin "7") (pinfunction "7_7") (pintype "passive"))
      (node (ref "LED2") (pin "C") (pinfunction "C_C") (pintype "passive"))
      (node (ref "R3") (pin "2") (pinfunction "2_2") (pintype "passive"))
      (node (ref "R5") (pin "1") (pinfunction "1_1") (pintype "passive"))
      (node (ref "SJ1") (pin "2") (pinfunction "2_2") (pintype "passive"))
      (node (ref "SW1") (pin "1") (pinfunction "P_1") (pintype "passive"))
      (node (ref "SW1") (pin "MT1") (pinfunction "MT_MT1") (pintype "bidirectional"))
      (node (ref "SW1") (pin "MT2") (pinfunction "MT_MT2") (pintype "bidirectional"))
      (node (ref "U1") (pin "2") (pinfunction "VSS_2") (pintype "power_in"))
      (node (ref "X3") (pin "1") (pinfunction "1_1") (pintype "passive"))
      (node (ref "X3") (pin "NC1") (pinfunction "P$1_NC1") (pintype "bidirectional"))
      (node (ref "X3") (pin "NC2") (pinfunction "P$1_NC2") (pintype "bidirectional"))
    )
    (net (code "33") (name "Net-(LED1-PadC)") (class "Default")
      (node (ref "LED1") (pin "C") (pinfunction "C_C") (pintype "passive"))
      (node (ref "R1") (pin "1") (pinfunction "1_1") (pintype "passive"))
    )
    (net (code "34") (name "Net-(LED2-PadA)") (class "Default")
      (node (ref "LED2") (pin "A") (pinfunction "A_A") (pintype "passive"))
      (node (ref "R2") (pin "1") (pinfunction "1_1") (pintype "passive"))
    )
    (net (code "35") (name "Net-(R4-Pad2)") (class "Default")
      (node (ref "R4") (pin "2") (pinfunction "2_2") (pintype "passive"))
      (node (ref "SJ1") (pin "1") (pinfunction "1_1") (pintype "passive"))
    )
    (net (code "36") (name "Net-(U1-PROG)") (class "Default")
      (node (ref "R3") (pin "1") (pinfunction "1_1") (pintype "passive"))
      (node (ref "R4") (pin "1") (pinfunction "1_1") (pintype "passive"))
      (node (ref "U1") (pin "5") (pinfunction "PROG_5") (pintype "input"))
    )
    (net (code "37") (name "Net-(U1-STAT)") (class "Default")
      (node (ref "R1") (pin "2") (pinfunction "2_2") (pintype "passive"))
      (node (ref "R2") (pin "2") (pinfunction "2_2") (pintype "passive"))
      (node (ref "U1") (pin "1") (pinfunction "STAT_1") (pintype "output"))
    )
    (net (code "38") (name "Net-(U1-VBAT)") (class "Default")
      (node (ref "SJ2") (pin "1") (pinfunction "1_1") (pintype "passive"))
      (node (ref "U1") (pin "3") (pinfunction "VBAT_3") (pintype "power_in"))
    )
    (net (code "39") (name "VBAT") (class "Default")
      (node (ref "C2") (pin "1") (pinfunction "1_1") (pintype "passive"))
      (node (ref "Q3") (pin "3") (pinfunction "D_3") (pintype "passive"))
      (node (ref "SJ2") (pin "2") (pinfunction "2_2") (pintype "passive"))
      (node (ref "X3") (pin "2") (pinfunction "2_2") (pintype "passive"))
    )
    (net (code "40") (name "VBUS") (class "Default")
      (node (ref "C1") (pin "1") (pinfunction "1_1") (pintype "passive"))
      (node (ref "CB1") (pin "S79") (pinfunction "VBUS_S79") (pintype "power_in"))
      (node (ref "CB1") (pin "S80") (pinfunction "VBUS_S80") (pintype "power_in"))
      (node (ref "CB1") (pin "T79") (pinfunction "VBUS_T79") (pintype "power_in"))
      (node (ref "CB1") (pin "T80") (pinfunction "VBUS_T80") (pintype "power_in"))
      (node (ref "CB2") (pin "S79") (pinfunction "VBUS_S79") (pintype "power_in"))
      (node (ref "CB2") (pin "S80") (pinfunction "VBUS_S80") (pintype "power_in"))
      (node (ref "CB2") (pin "T79") (pinfunction "VBUS_T79") (pintype "power_in"))
      (node (ref "CB2") (pin "T80") (pinfunction "VBUS_T80") (pintype "power_in"))
      (node (ref "JP2") (pin "1") (pinfunction "1_1") (pintype "passive"))
      (node (ref "LED1") (pin "A") (pinfunction "A_A") (pintype "passive"))
      (node (ref "Q3") (pin "1") (pinfunction "G_1") (pintype "passive"))
      (node (ref "R5") (pin "2") (pinfunction "2_2") (pintype "passive"))
      (node (ref "U1") (pin "4") (pinfunction "VDD_4") (pintype "power_in"))
    )
    (net (code "41") (name "unconnected-(ENA_SW-S-PadC)") (class "Default")
      (node (ref "ENA_SW") (pin "C") (pinfunction "S_C") (pintype "passive"))
    )
  )
)
